# Schematic_openbook_v58.net
KiCad netlist of a schematic drawn in EAGLE
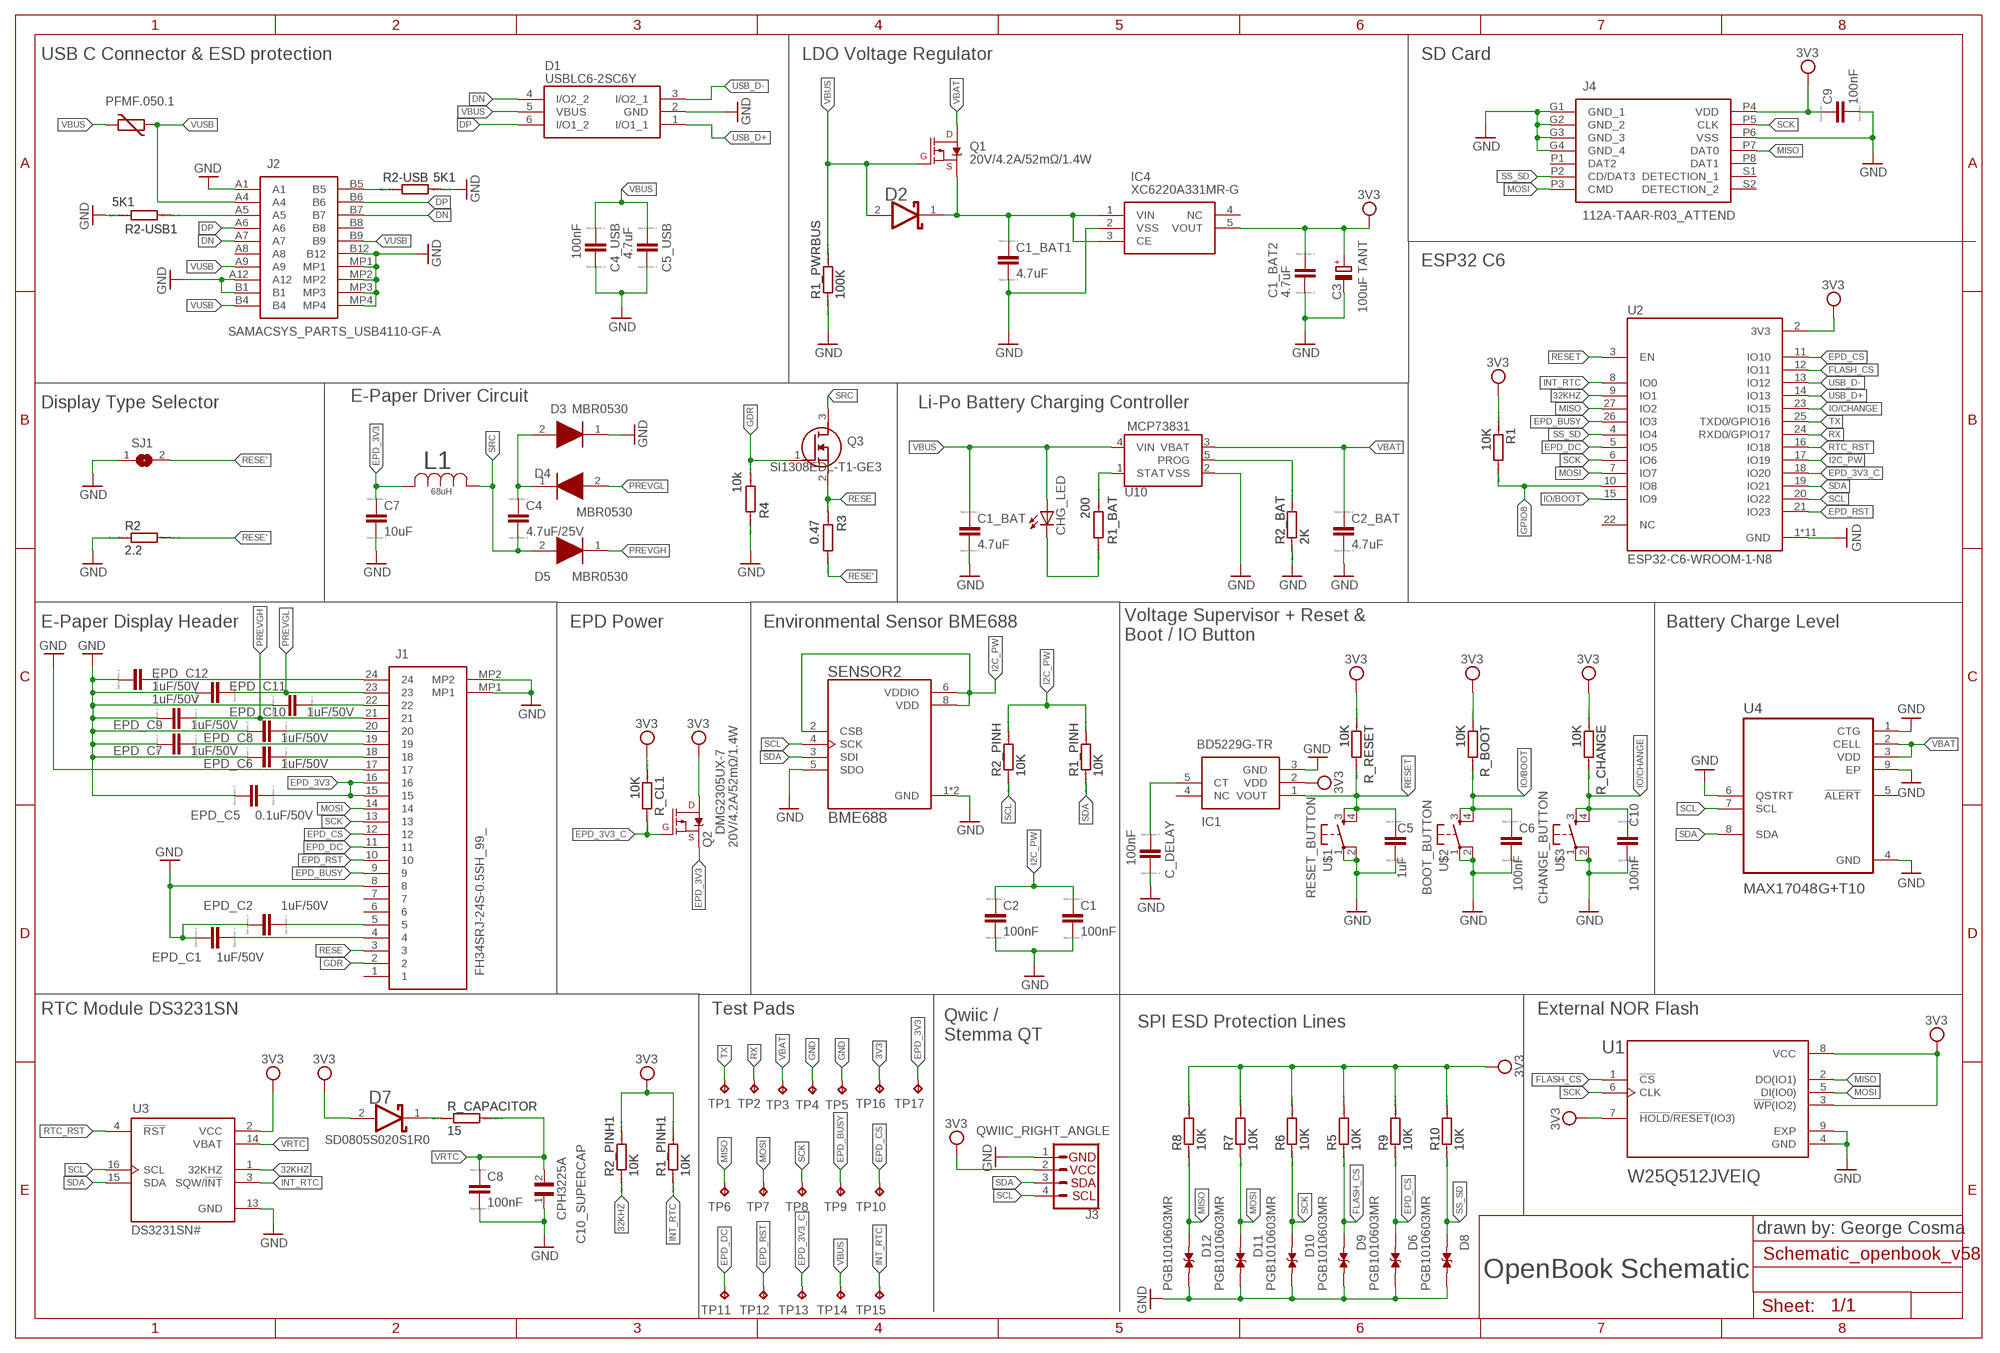
[diagram p0: schematic, sheet 1]

(export (version "E")
  (design (tool "Eeschema 10.0.6"))
  (components
    (comp (ref "C1")
      (value "100nF")
      (footprint "eagle-import:EAGLE-LTSPICE_C0402")
      (libsource (lib "eagle-import") (part "EAGLE-LTSPICE_CC0402"))
    )
    (comp (ref "C1_BAT")
      (value "4.7uF")
      (footprint "eagle-import:EAGLE-LTSPICE_C0402")
      (libsource (lib "eagle-import") (part "EAGLE-LTSPICE_CC0402"))
    )
    (comp (ref "C1_BAT1")
      (value "4.7uF")
      (footprint "eagle-import:EAGLE-LTSPICE_C0402")
      (libsource (lib "eagle-import") (part "EAGLE-LTSPICE_CC0402"))
    )
    (comp (ref "C1_BAT2")
      (value "4.7uF")
      (footprint "eagle-import:EAGLE-LTSPICE_C0402")
      (libsource (lib "eagle-import") (part "EAGLE-LTSPICE_CC0402"))
    )
    (comp (ref "C2")
      (value "100nF")
      (footprint "eagle-import:EAGLE-LTSPICE_C0402")
      (libsource (lib "eagle-import") (part "EAGLE-LTSPICE_CC0402"))
    )
    (comp (ref "C2_BAT")
      (value "4.7uF")
      (footprint "eagle-import:EAGLE-LTSPICE_C0402")
      (libsource (lib "eagle-import") (part "EAGLE-LTSPICE_CC0402"))
    )
    (comp (ref "C3")
      (value "100uF TANT")
      (footprint "eagle-import:RCL_CT3528")
      (libsource (lib "eagle-import") (part "RCL_CPOL-EUCT3528"))
    )
    (comp (ref "C4")
      (value "4.7uF/25V")
      (footprint "eagle-import:EAGLE-LTSPICE_C0402")
      (libsource (lib "eagle-import") (part "EAGLE-LTSPICE_CC0402"))
    )
    (comp (ref "C4_USB")
      (value "100nF")
      (footprint "eagle-import:EAGLE-LTSPICE_C0402")
      (libsource (lib "eagle-import") (part "EAGLE-LTSPICE_CC0402"))
    )
    (comp (ref "C5")
      (value "1uF")
      (footprint "eagle-import:EAGLE-LTSPICE_C0402")
      (libsource (lib "eagle-import") (part "EAGLE-LTSPICE_CC0402"))
    )
    (comp (ref "C5_USB")
      (value "4.7uF")
      (footprint "eagle-import:EAGLE-LTSPICE_C0402")
      (libsource (lib "eagle-import") (part "EAGLE-LTSPICE_CC0402"))
    )
    (comp (ref "C6")
      (value "100nF")
      (footprint "eagle-import:EAGLE-LTSPICE_C0402")
      (libsource (lib "eagle-import") (part "EAGLE-LTSPICE_CC0402"))
    )
    (comp (ref "C7")
      (value "10uF")
      (footprint "eagle-import:EAGLE-LTSPICE_C0402")
      (libsource (lib "eagle-import") (part "EAGLE-LTSPICE_CC0402"))
    )
    (comp (ref "C8")
      (value "100nF")
      (footprint "eagle-import:EAGLE-LTSPICE_C0402")
      (libsource (lib "eagle-import") (part "EAGLE-LTSPICE_CC0402"))
    )
    (comp (ref "C9")
      (value "100nF")
      (footprint "eagle-import:EAGLE-LTSPICE_C0402")
      (libsource (lib "eagle-import") (part "EAGLE-LTSPICE_CC0402"))
    )
    (comp (ref "C10")
      (value "100nF")
      (footprint "eagle-import:EAGLE-LTSPICE_C0402")
      (libsource (lib "eagle-import") (part "EAGLE-LTSPICE_CC0402"))
    )
    (comp (ref "C10_SUPERCAP")
      (value "CPH3225A")
      (footprint "eagle-import:CAPCP3225X100N")
      (fields (field (name "MF") "Seiko Instruments"))
      (libsource (lib "eagle-import") (part "CPH3225A"))
    )
    (comp (ref "CHG_LED")
      (value "NA")
      (footprint "eagle-import:ADAFRUIT_CHIP-LED0603")
      (libsource (lib "eagle-import") (part "ADAFRUIT_LEDCHIP-LED0603"))
    )
    (comp (ref "C_DELAY")
      (value "100nF")
      (footprint "eagle-import:EAGLE-LTSPICE_C0402")
      (libsource (lib "eagle-import") (part "EAGLE-LTSPICE_CC0402"))
    )
    (comp (ref "D1")
      (value "USBLC6-2SC6Y")
      (footprint "eagle-import:SOT95P280X145-6N")
      (fields (field (name "MF") "STMicroelectronics"))
      (libsource (lib "eagle-import") (part "USBLC6-2SC6Y"))
    )
    (comp (ref "D2")
      (value "ESP32_WROVER_AVX---SD0805S020S1R0_AVX_SD0805S020S1R0_0_0AVX_SD0805S020S1R0_0_0")
      (footprint "eagle-import:ESP32_WROVER_AVX---SD0805S020S1R0_AVX_SD0805S020S1R0_0")
      (fields
        (field (name "DIGIKEY_PART_NUMBER") "478-7800-1-ND")
        (field (name "MF") "AVX")
        (field (name "MOUSER_PART_NUMBER") "581-SD0805S020S1R0")
      )
      (libsource (lib "eagle-import") (part "ESP32_WROVER_AVX---SD0805S020S1R0_AVX_SD0805S020S1R0_0_0AVX_SD0805S020S1R0_0_0"))
    )
    (comp (ref "D3")
      (value "MBR0530")
      (footprint "eagle-import:SOD3716X135N")
      (fields (field (name "MF") "ON Semiconductor"))
      (libsource (lib "eagle-import") (part "MBR0530"))
    )
    (comp (ref "D4")
      (value "MBR0530")
      (footprint "eagle-import:SOD3716X135N")
      (fields (field (name "MF") "ON Semiconductor"))
      (libsource (lib "eagle-import") (part "MBR0530"))
    )
    (comp (ref "D5")
      (value "MBR0530")
      (footprint "eagle-import:SOD3716X135N")
      (fields (field (name "MF") "ON Semiconductor"))
      (libsource (lib "eagle-import") (part "MBR0530"))
    )
    (comp (ref "D6")
      (value "PGB1010603MR")
      (footprint "eagle-import:DIOC1608X36N")
      (fields (field (name "MF") "Littelfuse Inc."))
      (libsource (lib "eagle-import") (part "PGB1010603MR"))
    )
    (comp (ref "D7")
      (value "SD0805S020S1R0")
      (footprint "eagle-import:ESP32_WROVER_AVX---SD0805S020S1R0_AVX_SD0805S020S1R0_0")
      (fields
        (field (name "DIGIKEY_PART_NUMBER") "478-7800-1-ND")
        (field (name "MF") "AVX")
        (field (name "MOUSER_PART_NUMBER") "581-SD0805S020S1R0")
      )
      (libsource (lib "eagle-import") (part "ESP32_WROVER_AVX---SD0805S020S1R0_AVX_SD0805S020S1R0_0_0AVX_SD0805S020S1R0_0_0"))
    )
    (comp (ref "D8")
      (value "PGB1010603MR")
      (footprint "eagle-import:DIOC1608X36N")
      (fields (field (name "MF") "Littelfuse Inc."))
      (libsource (lib "eagle-import") (part "PGB1010603MR"))
    )
    (comp (ref "D9")
      (value "PGB1010603MR")
      (footprint "eagle-import:DIOC1608X36N")
      (fields (field (name "MF") "Littelfuse Inc."))
      (libsource (lib "eagle-import") (part "PGB1010603MR"))
    )
    (comp (ref "D10")
      (value "PGB1010603MR")
      (footprint "eagle-import:DIOC1608X36N")
      (fields (field (name "MF") "Littelfuse Inc."))
      (libsource (lib "eagle-import") (part "PGB1010603MR"))
    )
    (comp (ref "D11")
      (value "PGB1010603MR")
      (footprint "eagle-import:DIOC1608X36N")
      (fields (field (name "MF") "Littelfuse Inc."))
      (libsource (lib "eagle-import") (part "PGB1010603MR"))
    )
    (comp (ref "D12")
      (value "PGB1010603MR")
      (footprint "eagle-import:DIOC1608X36N")
      (fields (field (name "MF") "Littelfuse Inc."))
      (libsource (lib "eagle-import") (part "PGB1010603MR"))
    )
    (comp (ref "EPD_C1")
      (value "1uF/50V")
      (footprint "eagle-import:EAGLE-LTSPICE_C0402")
      (libsource (lib "eagle-import") (part "EAGLE-LTSPICE_CC0402"))
    )
    (comp (ref "EPD_C2")
      (value "1uF/50V")
      (footprint "eagle-import:EAGLE-LTSPICE_C0402")
      (libsource (lib "eagle-import") (part "EAGLE-LTSPICE_CC0402"))
    )
    (comp (ref "EPD_C5")
      (value "0.1uF/50V")
      (footprint "eagle-import:EAGLE-LTSPICE_C0402")
      (libsource (lib "eagle-import") (part "EAGLE-LTSPICE_CC0402"))
    )
    (comp (ref "EPD_C6")
      (value "1uF/50V")
      (footprint "eagle-import:EAGLE-LTSPICE_C0402")
      (libsource (lib "eagle-import") (part "EAGLE-LTSPICE_CC0402"))
    )
    (comp (ref "EPD_C7")
      (value "1uF/50V")
      (footprint "eagle-import:EAGLE-LTSPICE_C0402")
      (libsource (lib "eagle-import") (part "EAGLE-LTSPICE_CC0402"))
    )
    (comp (ref "EPD_C8")
      (value "1uF/50V")
      (footprint "eagle-import:EAGLE-LTSPICE_C0402")
      (libsource (lib "eagle-import") (part "EAGLE-LTSPICE_CC0402"))
    )
    (comp (ref "EPD_C9")
      (value "1uF/50V")
      (footprint "eagle-import:EAGLE-LTSPICE_C0402")
      (libsource (lib "eagle-import") (part "EAGLE-LTSPICE_CC0402"))
    )
    (comp (ref "EPD_C10")
      (value "1uF/50V")
      (footprint "eagle-import:EAGLE-LTSPICE_C0402")
      (libsource (lib "eagle-import") (part "EAGLE-LTSPICE_CC0402"))
    )
    (comp (ref "EPD_C11")
      (value "1uF/50V")
      (footprint "eagle-import:EAGLE-LTSPICE_C0402")
      (libsource (lib "eagle-import") (part "EAGLE-LTSPICE_CC0402"))
    )
    (comp (ref "EPD_C12")
      (value "1uF/50V")
      (footprint "eagle-import:EAGLE-LTSPICE_C0402")
      (libsource (lib "eagle-import") (part "EAGLE-LTSPICE_CC0402"))
    )
    (comp (ref "IC1")
      (value "BD5229G-TR")
      (footprint "eagle-import:SOT95P280X125-5N")
      (fields (field (name "MOUSER_PART_NUMBER") "755-BD5229G-TR"))
      (libsource (lib "eagle-import") (part "BD5229G-TR"))
    )
    (comp (ref "IC4")
      (value "XC6220A331MR-G")
      (footprint "eagle-import:SOT95P280X120-5N")
      (fields (field (name "MOUSER_PART_NUMBER") "865-XC6220A331MR-G"))
      (libsource (lib "eagle-import") (part "XC6220A331MR-G"))
    )
    (comp (ref "J1")
      (value "FH34SRJ-24S-0.5SH_99_")
      (footprint "eagle-import:FH34SRJ24S05SH99")
      (fields
        (field (name "MANUFACTURER_PART_NUMBER") "FH34SRJ-24S-0.5SH(99)")
        (field (name "MOUSER_PART_NUMBER") "798-FH34SRJ24S05SH99")
      )
      (libsource (lib "eagle-import") (part "FH34SRJ-24S-0.5SH_99_"))
    )
    (comp (ref "J2")
      (value "SAMACSYS_PARTS_USB4110-GF-A")
      (footprint "eagle-import:SAMACSYS_PARTS_USB4110GFA")
      (fields
        (field (name "MANUFACTURER_PART_NUMBER") "USB4110-GF-A")
        (field (name "MOUSER_PART_NUMBER") "640-USB4110-GF-A")
      )
      (libsource (lib "eagle-import") (part "SAMACSYS_PARTS_USB4110-GF-A"))
    )
    (comp (ref "J3")
      (value "QWIIC_RIGHT_ANGLE")
      (footprint "eagle-import:JST04_1MM_RA")
      (libsource (lib "eagle-import") (part "QWIIC_CONNECTORJS-1MM"))
    )
    (comp (ref "J4")
      (value "112A-TAAR-R03_ATTEND")
      (footprint "eagle-import:112ATAARR03ATTEND")
      (fields (field (name "MANUFACTURER_PART_NUMBER") "112A-TAAR-R03 ATTEND"))
      (libsource (lib "eagle-import") (part "112A-TAAR-R03_ATTEND"))
    )
    (comp (ref "L1")
      (value "68uH")
      (footprint "eagle-import:IND_4828-WE-TPC_WRE")
      (fields
        (field (name "MANUFACTURER_PART_NUMBER") "744043680")
        (field (name "COPYRIGHT") "Copyright (C) 2024 Ultra Librarian. All rights reserved.")
      )
      (libsource (lib "eagle-import") (part "744043680IND_4828-WE-TPC_WRE"))
    )
    (comp (ref "PFMF.050.1")
      (value "ESP32C6_VARISTORCN1812")
      (footprint "eagle-import:ESP32C6_VARISTOR_CT_CN1812")
      (libsource (lib "eagle-import") (part "ESP32C6_VARISTORCN1812"))
    )
    (comp (ref "Q1")
      (value "20V/4.2A/52mΩ/1.4W")
      (footprint "eagle-import:ESP32_WROVER_SPARKFUN-DISCRETESEMI_SOT23-3")
      (libsource (lib "eagle-import") (part "ESP32_WROVER_SPARKFUN-DISCRETESEMI_MOSFET_PCH-DMG2305UX-7"))
    )
    (comp (ref "Q2")
      (value "20V/4.2A/52mΩ/1.4W")
      (footprint "eagle-import:ESP32_WROVER_SPARKFUN-DISCRETESEMI_SOT23-3")
      (libsource (lib "eagle-import") (part "ESP32_WROVER_SPARKFUN-DISCRETESEMI_MOSFET_PCH-DMG2305UX-7"))
    )
    (comp (ref "Q3")
      (value "SI1308EDL-T1-GE3")
      (footprint "eagle-import:SOT65P210X110-3N")
      (fields (field (name "MF") "Vishay Siliconix"))
      (libsource (lib "eagle-import") (part "SI1308EDL-T1-GE3"))
    )
    (comp (ref "R1")
      (value "10K")
      (footprint "eagle-import:ESP32_WROVER_EAGLE-LTSPICE_R0402")
      (libsource (lib "eagle-import") (part "ESP32_WROVER_EAGLE-LTSPICE_RR0402"))
    )
    (comp (ref "R1_BAT")
      (value "200")
      (footprint "eagle-import:ESP32_WROVER_EAGLE-LTSPICE_R0402")
      (libsource (lib "eagle-import") (part "ESP32_WROVER_EAGLE-LTSPICE_RR0402"))
    )
    (comp (ref "R1_PINH")
      (value "10K")
      (footprint "eagle-import:ESP32_WROVER_EAGLE-LTSPICE_R0402")
      (libsource (lib "eagle-import") (part "ESP32_WROVER_EAGLE-LTSPICE_RR0402"))
    )
    (comp (ref "R1_PINH1")
      (value "10K")
      (footprint "eagle-import:ESP32_WROVER_EAGLE-LTSPICE_R0402")
      (libsource (lib "eagle-import") (part "ESP32_WROVER_EAGLE-LTSPICE_RR0402"))
    )
    (comp (ref "R1_PWRBUS")
      (value "100K")
      (footprint "eagle-import:ESP32_WROVER_EAGLE-LTSPICE_R0402")
      (libsource (lib "eagle-import") (part "ESP32_WROVER_EAGLE-LTSPICE_RR0402"))
    )
    (comp (ref "R2")
      (value "2.2")
      (footprint "eagle-import:ESP32_WROVER_EAGLE-LTSPICE_R0402")
      (libsource (lib "eagle-import") (part "ESP32_WROVER_EAGLE-LTSPICE_RR0402"))
    )
    (comp (ref "R2-USB")
      (value "5K1")
      (footprint "eagle-import:ESP32_WROVER_EAGLE-LTSPICE_R0402")
      (libsource (lib "eagle-import") (part "ESP32_WROVER_EAGLE-LTSPICE_RR0402"))
    )
    (comp (ref "R2-USB1")
      (value "5K1")
      (footprint "eagle-import:ESP32_WROVER_EAGLE-LTSPICE_R0402")
      (libsource (lib "eagle-import") (part "ESP32_WROVER_EAGLE-LTSPICE_RR0402"))
    )
    (comp (ref "R2_BAT")
      (value "2K")
      (footprint "eagle-import:ESP32_WROVER_EAGLE-LTSPICE_R0402")
      (libsource (lib "eagle-import") (part "ESP32_WROVER_EAGLE-LTSPICE_RR0402"))
    )
    (comp (ref "R2_PINH")
      (value "10K")
      (footprint "eagle-import:ESP32_WROVER_EAGLE-LTSPICE_R0402")
      (libsource (lib "eagle-import") (part "ESP32_WROVER_EAGLE-LTSPICE_RR0402"))
    )
    (comp (ref "R2_PINH1")
      (value "10K")
      (footprint "eagle-import:ESP32_WROVER_EAGLE-LTSPICE_R0402")
      (libsource (lib "eagle-import") (part "ESP32_WROVER_EAGLE-LTSPICE_RR0402"))
    )
    (comp (ref "R3")
      (value "0.47")
      (footprint "eagle-import:ESP32_WROVER_EAGLE-LTSPICE_R0402")
      (libsource (lib "eagle-import") (part "ESP32_WROVER_EAGLE-LTSPICE_RR0402"))
    )
    (comp (ref "R4")
      (value "10k")
      (footprint "eagle-import:ESP32_WROVER_EAGLE-LTSPICE_R0402")
      (libsource (lib "eagle-import") (part "ESP32_WROVER_EAGLE-LTSPICE_RR0402"))
    )
    (comp (ref "R5")
      (value "10K")
      (footprint "eagle-import:ESP32_WROVER_EAGLE-LTSPICE_R0402")
      (libsource (lib "eagle-import") (part "ESP32_WROVER_EAGLE-LTSPICE_RR0402"))
    )
    (comp (ref "R6")
      (value "10K")
      (footprint "eagle-import:ESP32_WROVER_EAGLE-LTSPICE_R0402")
      (libsource (lib "eagle-import") (part "ESP32_WROVER_EAGLE-LTSPICE_RR0402"))
    )
    (comp (ref "R7")
      (value "10K")
      (footprint "eagle-import:ESP32_WROVER_EAGLE-LTSPICE_R0402")
      (libsource (lib "eagle-import") (part "ESP32_WROVER_EAGLE-LTSPICE_RR0402"))
    )
    (comp (ref "R8")
      (value "10K")
      (footprint "eagle-import:ESP32_WROVER_EAGLE-LTSPICE_R0402")
      (libsource (lib "eagle-import") (part "ESP32_WROVER_EAGLE-LTSPICE_RR0402"))
    )
    (comp (ref "R9")
      (value "10K")
      (footprint "eagle-import:ESP32_WROVER_EAGLE-LTSPICE_R0402")
      (libsource (lib "eagle-import") (part "ESP32_WROVER_EAGLE-LTSPICE_RR0402"))
    )
    (comp (ref "R10")
      (value "10K")
      (footprint "eagle-import:ESP32_WROVER_EAGLE-LTSPICE_R0402")
      (libsource (lib "eagle-import") (part "ESP32_WROVER_EAGLE-LTSPICE_RR0402"))
    )
    (comp (ref "R_BOOT")
      (value "10K")
      (footprint "eagle-import:ESP32_WROVER_EAGLE-LTSPICE_R0402")
      (libsource (lib "eagle-import") (part "ESP32_WROVER_EAGLE-LTSPICE_RR0402"))
    )
    (comp (ref "R_CAPACITOR")
      (value "15")
      (footprint "eagle-import:ESP32_WROVER_EAGLE-LTSPICE_R0402")
      (libsource (lib "eagle-import") (part "ESP32_WROVER_EAGLE-LTSPICE_RR0402"))
    )
    (comp (ref "R_CHANGE")
      (value "10K")
      (footprint "eagle-import:ESP32_WROVER_EAGLE-LTSPICE_R0402")
      (libsource (lib "eagle-import") (part "ESP32_WROVER_EAGLE-LTSPICE_RR0402"))
    )
    (comp (ref "R_CL1")
      (value "10K")
      (footprint "eagle-import:ESP32_WROVER_EAGLE-LTSPICE_R0402")
      (libsource (lib "eagle-import") (part "ESP32_WROVER_EAGLE-LTSPICE_RR0402"))
    )
    (comp (ref "R_RESET")
      (value "10K")
      (footprint "eagle-import:ESP32_WROVER_EAGLE-LTSPICE_R0402")
      (libsource (lib "eagle-import") (part "ESP32_WROVER_EAGLE-LTSPICE_RR0402"))
    )
    (comp (ref "SENSOR2")
      (value "BME688")
      (footprint "eagle-import:ESP32_WROVER_BME680_PSON80P300X300X100-8N")
      (fields (field (name "MF") "Bosch Sensortec") (field (name "MP") "BME680"))
      (libsource (lib "eagle-import") (part "ESP32_WROVER_BME680_BME680"))
    )
    (comp (ref "SJ1") (value "NA") (footprint "eagle-import:SJ") (libsource (lib "eagle-import") (part "SJ")))
    (comp (ref "TP1")
      (value "TPTP20R")
      (footprint "eagle-import:TP20R")
      (libsource (lib "eagle-import") (part "TPTP20R"))
    )
    (comp (ref "TP2")
      (value "TPTP20R")
      (footprint "eagle-import:TP20R")
      (libsource (lib "eagle-import") (part "TPTP20R"))
    )
    (comp (ref "TP3")
      (value "TPTP20R")
      (footprint "eagle-import:TP20R")
      (libsource (lib "eagle-import") (part "TPTP20R"))
    )
    (comp (ref "TP4")
      (value "TPTP20R")
      (footprint "eagle-import:TP20R")
      (libsource (lib "eagle-import") (part "TPTP20R"))
    )
    (comp (ref "TP5")
      (value "TPTP20R")
      (footprint "eagle-import:TP20R")
      (libsource (lib "eagle-import") (part "TPTP20R"))
    )
    (comp (ref "TP6")
      (value "TPTP20R")
      (footprint "eagle-import:TP20R")
      (libsource (lib "eagle-import") (part "TPTP20R"))
    )
    (comp (ref "TP7")
      (value "TPTP20R")
      (footprint "eagle-import:TP20R")
      (libsource (lib "eagle-import") (part "TPTP20R"))
    )
    (comp (ref "TP8")
      (value "TPTP20R")
      (footprint "eagle-import:TP20R")
      (libsource (lib "eagle-import") (part "TPTP20R"))
    )
    (comp (ref "TP9")
      (value "TPTP20R")
      (footprint "eagle-import:TP20R")
      (libsource (lib "eagle-import") (part "TPTP20R"))
    )
    (comp (ref "TP10")
      (value "TPTP20R")
      (footprint "eagle-import:TP20R")
      (libsource (lib "eagle-import") (part "TPTP20R"))
    )
    (comp (ref "TP11")
      (value "TPTP20R")
      (footprint "eagle-import:TP20R")
      (libsource (lib "eagle-import") (part "TPTP20R"))
    )
    (comp (ref "TP12")
      (value "TPTP20R")
      (footprint "eagle-import:TP20R")
      (libsource (lib "eagle-import") (part "TPTP20R"))
    )
    (comp (ref "TP13")
      (value "TPTP20R")
      (footprint "eagle-import:TP20R")
      (libsource (lib "eagle-import") (part "TPTP20R"))
    )
    (comp (ref "TP14")
      (value "TPTP20R")
      (footprint "eagle-import:TP20R")
      (libsource (lib "eagle-import") (part "TPTP20R"))
    )
    (comp (ref "TP15")
      (value "TPTP20R")
      (footprint "eagle-import:TP20R")
      (libsource (lib "eagle-import") (part "TPTP20R"))
    )
    (comp (ref "TP16")
      (value "TPTP20R")
      (footprint "eagle-import:TP20R")
      (libsource (lib "eagle-import") (part "TPTP20R"))
    )
    (comp (ref "TP17")
      (value "TPTP20R")
      (footprint "eagle-import:TP20R")
      (libsource (lib "eagle-import") (part "TPTP20R"))
    )
    (comp (ref "U$1")
      (value "RESET_BUTTON")
      (footprint "eagle-import:MYBUTTON")
      (libsource (lib "eagle-import") (part "BUTTON_CUSYOMV1"))
    )
    (comp (ref "U$2")
      (value "BOOT_BUTTON")
      (footprint "eagle-import:MYBUTTON")
      (libsource (lib "eagle-import") (part "BUTTON_CUSYOMV1"))
    )
    (comp (ref "U$3")
      (value "CHANGE_BUTTON")
      (footprint "eagle-import:MYBUTTON")
      (libsource (lib "eagle-import") (part "BUTTON_CUSYOMV1"))
    )
    (comp (ref "U1")
      (value "W25Q512JVEIQ")
      (footprint "eagle-import:SON127P600X800X80-9N")
      (fields (field (name "MF") "Winbond Electronics"))
      (libsource (lib "eagle-import") (part "W25Q512JVEIQ"))
    )
    (comp (ref "U2")
      (value "ESP32-C6-WROOM-1-N8")
      (footprint "eagle-import:XCVR_ESP32-C6-WROOM-1-N8")
      (fields (field (name "MF") "Espressif Systems"))
      (libsource (lib "eagle-import") (part "ESP32-C6-WROOM-1-N8"))
    )
    (comp (ref "U3")
      (value "DS3231SN#")
      (footprint "eagle-import:SOIC127P1032X265-16N")
      (fields (field (name "MF") "Analog Devices"))
      (libsource (lib "eagle-import") (part "DS3231SN#"))
    )
    (comp (ref "U4")
      (value "MAX17048G+T10")
      (footprint "eagle-import:SON50P200X200X80-9N")
      (fields (field (name "MF") "Analog Devices"))
      (libsource (lib "eagle-import") (part "MAX17048G+T10"))
    )
    (comp (ref "U10")
      (value "MCP73831")
      (footprint "eagle-import:ESP32_WROVER_SPARKFUN-IC-POWER_SOT23-5")
      (libsource (lib "eagle-import") (part "ESP32_WROVER_SPARKFUN-IC-POWER_MCP73831"))
    )
  )
  (nets
    (net (code "1") (name "3V3") (class "Default")
      (node (ref "C1_BAT2") (pin "1") (pinfunction "1_1") (pintype "passive"))
      (node (ref "C3") (pin "+") (pinfunction "+_+") (pintype "passive"))
      (node (ref "C9") (pin "1") (pinfunction "1_1") (pintype "passive"))
      (node (ref "D7") (pin "2") (pinfunction "ANODE_2") (pintype "bidirectional"))
      (node (ref "IC1") (pin "2") (pinfunction "VDD_2") (pintype "bidirectional"))
      (node (ref "IC4") (pin "5") (pinfunction "VOUT_5") (pintype "bidirectional"))
      (node (ref "J3") (pin "2") (pinfunction "2_2") (pintype "power_in"))
      (node (ref "J4") (pin "P4") (pinfunction "VDD_P4") (pintype "bidirectional"))
      (node (ref "Q2") (pin "3") (pinfunction "D_3") (pintype "bidirectional"))
      (node (ref "R1") (pin "1") (pinfunction "1_1") (pintype "passive"))
      (node (ref "R10") (pin "2") (pinfunction "2_2") (pintype "passive"))
      (node (ref "R1_PINH1") (pin "2") (pinfunction "2_2") (pintype "passive"))
      (node (ref "R2_PINH1") (pin "2") (pinfunction "2_2") (pintype "passive"))
      (node (ref "R5") (pin "2") (pinfunction "2_2") (pintype "passive"))
      (node (ref "R6") (pin "2") (pinfunction "2_2") (pintype "passive"))
      (node (ref "R7") (pin "2") (pinfunction "2_2") (pintype "passive"))
      (node (ref "R8") (pin "2") (pinfunction "2_2") (pintype "passive"))
      (node (ref "R9") (pin "2") (pinfunction "2_2") (pintype "passive"))
      (node (ref "R_BOOT") (pin "1") (pinfunction "1_1") (pintype "passive"))
      (node (ref "R_CHANGE") (pin "1") (pinfunction "1_1") (pintype "passive"))
      (node (ref "R_CL1") (pin "1") (pinfunction "1_1") (pintype "passive"))
      (node (ref "R_RESET") (pin "1") (pinfunction "1_1") (pintype "passive"))
      (node (ref "TP16") (pin "TP") (pinfunction "TP_TP") (pintype "input"))
      (node (ref "U1") (pin "3") (pinfunction "~{WP}(IO2)_3") (pintype "bidirectional"))
      (node (ref "U1") (pin "7") (pinfunction "~{HOLD}/~{RESET}(IO3)_7") (pintype "bidirectional"))
      (node (ref "U1") (pin "8") (pinfunction "VCC_8") (pintype "power_in"))
      (node (ref "U2") (pin "2") (pinfunction "3V3_2") (pintype "power_in"))
      (node (ref "U3") (pin "2") (pinfunction "VCC_2") (pintype "power_in"))
    )
    (net (code "2") (name "32KHZ") (class "Default")
      (node (ref "R2_PINH1") (pin "1") (pinfunction "1_1") (pintype "passive"))
      (node (ref "U2") (pin "9") (pinfunction "IO1_9") (pintype "bidirectional"))
      (node (ref "U3") (pin "1") (pinfunction "32KHZ_1") (pintype "output"))
    )
    (net (code "3") (name "DN") (class "Default")
      (node (ref "D1") (pin "4") (pinfunction "I/O2_2_4") (pintype "bidirectional"))
      (node (ref "J2") (pin "A7") (pinfunction "A7_A7") (pintype "bidirectional"))
      (node (ref "J2") (pin "B7") (pinfunction "B7_B7") (pintype "bidirectional"))
    )
    (net (code "4") (name "DP") (class "Default")
      (node (ref "D1") (pin "6") (pinfunction "I/O1_2_6") (pintype "bidirectional"))
      (node (ref "J2") (pin "A6") (pinfunction "A6_A6") (pintype "bidirectional"))
      (node (ref "J2") (pin "B6") (pinfunction "B6_B6") (pintype "bidirectional"))
    )
    (net (code "5") (name "EPD_3V3") (class "Default")
      (node (ref "C7") (pin "1") (pinfunction "1_1") (pintype "passive"))
      (node (ref "EPD_C5") (pin "1") (pinfunction "1_1") (pintype "passive"))
      (node (ref "J1") (pin "15") (pinfunction "15_15") (pintype "bidirectional"))
      (node (ref "J1") (pin "16") (pinfunction "16_16") (pintype "bidirectional"))
      (node (ref "L1") (pin "2") (pinfunction "2_2") (pintype "passive"))
      (node (ref "Q2") (pin "2") (pinfunction "S_2") (pintype "bidirectional"))
      (node (ref "TP17") (pin "TP") (pinfunction "TP_TP") (pintype "input"))
    )
    (net (code "6") (name "EPD_3V3_C") (class "Default")
      (node (ref "Q2") (pin "1") (pinfunction "G_1") (pintype "bidirectional"))
      (node (ref "R_CL1") (pin "2") (pinfunction "2_2") (pintype "passive"))
      (node (ref "TP13") (pin "TP") (pinfunction "TP_TP") (pintype "input"))
      (node (ref "U2") (pin "18") (pinfunction "IO20_18") (pintype "bidirectional"))
    )
    (net (code "7") (name "EPD_BUSY") (class "Default")
      (node (ref "J1") (pin "9") (pinfunction "9_9") (pintype "bidirectional"))
      (node (ref "TP9") (pin "TP") (pinfunction "TP_TP") (pintype "input"))
      (node (ref "U2") (pin "26") (pinfunction "IO3_26") (pintype "bidirectional"))
    )
    (net (code "8") (name "EPD_CS") (class "Default")
      (node (ref "D6") (pin "1") (pinfunction "1_1") (pintype "passive"))
      (node (ref "J1") (pin "12") (pinfunction "12_12") (pintype "bidirectional"))
      (node (ref "R9") (pin "1") (pinfunction "1_1") (pintype "passive"))
      (node (ref "TP10") (pin "TP") (pinfunction "TP_TP") (pintype "input"))
      (node (ref "U2") (pin "11") (pinfunction "IO10_11") (pintype "bidirectional"))
    )
    (net (code "9") (name "EPD_DC") (class "Default")
      (node (ref "J1") (pin "11") (pinfunction "11_11") (pintype "bidirectional"))
      (node (ref "TP11") (pin "TP") (pinfunction "TP_TP") (pintype "input"))
      (node (ref "U2") (pin "5") (pinfunction "IO5_5") (pintype "bidirectional"))
    )
    (net (code "10") (name "EPD_RST") (class "Default")
      (node (ref "J1") (pin "10") (pinfunction "10_10") (pintype "bidirectional"))
      (node (ref "TP12") (pin "TP") (pinfunction "TP_TP") (pintype "input"))
      (node (ref "U2") (pin "21") (pinfunction "IO23_21") (pintype "bidirectional"))
    )
    (net (code "11") (name "FLASH_CS") (class "Default")
      (node (ref "D9") (pin "1") (pinfunction "1_1") (pintype "passive"))
      (node (ref "R5") (pin "1") (pinfunction "1_1") (pintype "passive"))
      (node (ref "U1") (pin "1") (pinfunction "~{CS}_1") (pintype "input"))
      (node (ref "U2") (pin "12") (pinfunction "IO11_12") (pintype "bidirectional"))
    )
    (net (code "12") (name "GDR") (class "Default")
      (node (ref "J1") (pin "2") (pinfunction "2_2") (pintype "bidirectional"))
      (node (ref "Q3") (pin "1") (pinfunction "G_1") (pintype "bidirectional"))
      (node (ref "R4") (pin "2") (pinfunction "2_2") (pintype "passive"))
    )
    (net (code "13") (name "GND") (class "Default")
      (node (ref "C1") (pin "2") (pinfunction "2_2") (pintype "passive"))
      (node (ref "C10") (pin "2") (pinfunction "2_2") (pintype "passive"))
      (node (ref "C10_SUPERCAP") (pin "1") (pinfunction "1_1") (pintype "passive"))
      (node (ref "C1_BAT") (pin "2") (pinfunction "2_2") (pintype "passive"))
      (node (ref "C1_BAT1") (pin "2") (pinfunction "2_2") (pintype "passive"))
      (node (ref "C1_BAT2") (pin "2") (pinfunction "2_2") (pintype "passive"))
      (node (ref "C2") (pin "2") (pinfunction "2_2") (pintype "passive"))
      (node (ref "C2_BAT") (pin "2") (pinfunction "2_2") (pintype "passive"))
      (node (ref "C3") (pin "-") (pinfunction "-_-") (pintype "passive"))
      (node (ref "C4_USB") (pin "2") (pinfunction "2_2") (pintype "passive"))
      (node (ref "C5") (pin "2") (pinfunction "2_2") (pintype "passive"))
      (node (ref "C5_USB") (pin "2") (pinfunction "2_2") (pintype "passive"))
      (node (ref "C6") (pin "2") (pinfunction "2_2") (pintype "passive"))
      (node (ref "C7") (pin "2") (pinfunction "2_2") (pintype "passive"))
      (node (ref "C8") (pin "2") (pinfunction "2_2") (pintype "passive"))
      (node (ref "C9") (pin "2") (pinfunction "2_2") (pintype "passive"))
      (node (ref "C_DELAY") (pin "2") (pinfunction "2_2") (pintype "passive"))
      (node (ref "D1") (pin "2") (pinfunction "GND_2") (pintype "bidirectional"))
      (node (ref "D10") (pin "2") (pinfunction "2_2") (pintype "passive"))
      (node (ref "D11") (pin "2") (pinfunction "2_2") (pintype "passive"))
      (node (ref "D12") (pin "2") (pinfunction "2_2") (pintype "passive"))
      (node (ref "D4") (pin "1") (pinfunction "K_1") (pintype "bidirectional"))
      (node (ref "D6") (pin "2") (pinfunction "2_2") (pintype "passive"))
      (node (ref "D8") (pin "2") (pinfunction "2_2") (pintype "passive"))
      (node (ref "D9") (pin "2") (pinfunction "2_2") (pintype "passive"))
      (node (ref "EPD_C1") (pin "2") (pinfunction "2_2") (pintype "passive"))
      (node (ref "EPD_C10") (pin "2") (pinfunction "2_2") (pintype "passive"))
      (node (ref "EPD_C11") (pin "2") (pinfunction "2_2") (pintype "passive"))
      (node (ref "EPD_C12") (pin "2") (pinfunction "2_2") (pintype "passive"))
      (node (ref "EPD_C2") (pin "2") (pinfunction "2_2") (pintype "passive"))
      (node (ref "EPD_C5") (pin "2") (pinfunction "2_2") (pintype "passive"))
      (node (ref "EPD_C6") (pin "2") (pinfunction "2_2") (pintype "passive"))
      (node (ref "EPD_C7") (pin "2") (pinfunction "2_2") (pintype "passive"))
      (node (ref "EPD_C8") (pin "2") (pinfunction "2_2") (pintype "passive"))
      (node (ref "EPD_C9") (pin "2") (pinfunction "2_2") (pintype "passive"))
      (node (ref "IC1") (pin "3") (pinfunction "GND_3") (pintype "bidirectional"))
      (node (ref "IC4") (pin "2") (pinfunction "VSS_2") (pintype "bidirectional"))
      (node (ref "J1") (pin "17") (pinfunction "17_17") (pintype "bidirectional"))
      (node (ref "J1") (pin "8") (pinfunction "8_8") (pintype "bidirectional"))
      (node (ref "J1") (pin "MP1") (pinfunction "MP1_MP1") (pintype "bidirectional"))
      (node (ref "J1") (pin "MP2") (pinfunction "MP2_MP2") (pintype "bidirectional"))
      (node (ref "J2") (pin "A1") (pinfunction "A1_A1") (pintype "bidirectional"))
      (node (ref "J2") (pin "A12") (pinfunction "A12_A12") (pintype "bidirectional"))
      (node (ref "J2") (pin "B1") (pinfunction "B1_B1") (pintype "bidirectional"))
      (node (ref "J2") (pin "B12") (pinfunction "B12_B12") (pintype "bidirectional"))
      (node (ref "J2") (pin "MP1") (pinfunction "MP1_MP1") (pintype "bidirectional"))
      (node (ref "J2") (pin "MP2") (pinfunction "MP2_MP2") (pintype "bidirectional"))
      (node (ref "J2") (pin "MP3") (pinfunction "MP3_MP3") (pintype "bidirectional"))
      (node (ref "J2") (pin "MP4") (pinfunction "MP4_MP4") (pintype "bidirectional"))
      (node (ref "J3") (pin "1") (pinfunction "1_1") (pintype "power_in"))
      (node (ref "J4") (pin "G1") (pinfunction "GND_1_G1") (pintype "bidirectional"))
      (node (ref "J4") (pin "G2") (pinfunction "GND_2_G2") (pintype "bidirectional"))
      (node (ref "J4") (pin "G3") (pinfunction "GND_3_G3") (pintype "bidirectional"))
      (node (ref "J4") (pin "G4") (pinfunction "GND_4_G4") (pintype "bidirectional"))
      (node (ref "J4") (pin "P6") (pinfunction "VSS_P6") (pintype "bidirectional"))
      (node (ref "R1_PWRBUS") (pin "1") (pinfunction "1_1") (pintype "passive"))
      (node (ref "R2") (pin "1") (pinfunction "1_1") (pintype "passive"))
      (node (ref "R2-USB") (pin "2") (pinfunction "2_2") (pintype "passive"))
      (node (ref "R2-USB1") (pin "1") (pinfunction "1_1") (pintype "passive"))
      (node (ref "R2_BAT") (pin "1") (pinfunction "1_1") (pintype "passive"))
      (node (ref "R4") (pin "1") (pinfunction "1_1") (pintype "passive"))
      (node (ref "SENSOR2") (pin "1") (pinfunction "GND_1") (pintype "power_in"))
      (node (ref "SENSOR2") (pin "5") (pinfunction "SDO_5") (pintype "bidirectional"))
      (node (ref "SENSOR2") (pin "7") (pinfunction "GND_7") (pintype "power_in"))
      (node (ref "SJ1") (pin "1") (pinfunction "1_1") (pintype "passive"))
      (node (ref "TP4") (pin "TP") (pinfunction "TP_TP") (pintype "input"))
      (node (ref "TP5") (pin "TP") (pinfunction "TP_TP") (pintype "input"))
      (node (ref "U$1") (pin "1") (pinfunction "1_1") (pintype "passive"))
      (node (ref "U$1") (pin "2") (pinfunction "2_2") (pintype "passive"))
      (node (ref "U$2") (pin "1") (pinfunction "1_1") (pintype "passive"))
      (node (ref "U$2") (pin "2") (pinfunction "2_2") (pintype "passive"))
      (node (ref "U$3") (pin "1") (pinfunction "1_1") (pintype "passive"))
      (node (ref "U$3") (pin "2") (pinfunction "2_2") (pintype "passive"))
      (node (ref "U1") (pin "4") (pinfunction "GND_4") (pintype "power_in"))
      (node (ref "U1") (pin "9") (pinfunction "EXP_9") (pintype "passive"))
      (node (ref "U10") (pin "2") (pinfunction "VSS_2") (pintype "power_in"))
      (node (ref "U2") (pin "1") (pinfunction "GND_1") (pintype "power_in"))
      (node (ref "U2") (pin "28") (pinfunction "GND_28") (pintype "power_in"))
      (node (ref "U2") (pin "29_1") (pinfunction "GND_29_1") (pintype "power_in"))
      (node (ref "U2") (pin "29_2") (pinfunction "GND_29_2") (pintype "power_in"))
      (node (ref "U2") (pin "29_3") (pinfunction "GND_29_3") (pintype "power_in"))
      (node (ref "U2") (pin "29_4") (pinfunction "GND_29_4") (pintype "power_in"))
      (node (ref "U2") (pin "29_5") (pinfunction "GND_29_5") (pintype "power_in"))
      (node (ref "U2") (pin "29_6") (pinfunction "GND_29_6") (pintype "power_in"))
      (node (ref "U2") (pin "29_7") (pinfunction "GND_29_7") (pintype "power_in"))
      (node (ref "U2") (pin "29_8") (pinfunction "GND_29_8") (pintype "power_in"))
      (node (ref "U2") (pin "29_9") (pinfunction "GND_29_9") (pintype "power_in"))
      (node (ref "U3") (pin "13") (pinfunction "GND_13") (pintype "power_in"))
      (node (ref "U4") (pin "1") (pinfunction "CTG_1") (pintype "power_in"))
      (node (ref "U4") (pin "4") (pinfunction "GND_4") (pintype "power_in"))
      (node (ref "U4") (pin "6") (pinfunction "QSTRT_6") (pintype "input"))
      (node (ref "U4") (pin "9") (pinfunction "EP_9") (pintype "power_in"))
    )
    (net (code "14") (name "GPIO8") (class "Default")
      (node (ref "R1") (pin "2") (pinfunction "2_2") (pintype "passive"))
      (node (ref "U2") (pin "10") (pinfunction "IO8_10") (pintype "bidirectional"))
    )
    (net (code "15") (name "I2C_PW") (class "Default")
      (node (ref "C1") (pin "1") (pinfunction "1_1") (pintype "passive"))
      (node (ref "C2") (pin "1") (pinfunction "1_1") (pintype "passive"))
      (node (ref "R1_PINH") (pin "2") (pinfunction "2_2") (pintype "passive"))
      (node (ref "R2_PINH") (pin "2") (pinfunction "2_2") (pintype "passive"))
      (node (ref "SENSOR2") (pin "2") (pinfunction "CSB_2") (pintype "input"))
      (node (ref "SENSOR2") (pin "6") (pinfunction "VDDIO_6") (pintype "power_in"))
      (node (ref "SENSOR2") (pin "8") (pinfunction "VDD_8") (pintype "power_in"))
      (node (ref "U2") (pin "17") (pinfunction "IO19_17") (pintype "bidirectional"))
    )
    (net (code "16") (name "INT_RTC") (class "Default")
      (node (ref "R1_PINH1") (pin "1") (pinfunction "1_1") (pintype "passive"))
      (node (ref "TP15") (pin "TP") (pinfunction "TP_TP") (pintype "input"))
      (node (ref "U2") (pin "8") (pinfunction "IO0_8") (pintype "bidirectional"))
      (node (ref "U3") (pin "3") (pinfunction "SQW/~{INT}_3") (pintype "output"))
    )
    (net (code "17") (name "IO{slash}BOOT") (class "Default")
      (node (ref "C6") (pin "1") (pinfunction "1_1") (pintype "passive"))
      (node (ref "R_BOOT") (pin "2") (pinfunction "2_2") (pintype "passive"))
      (node (ref "U$2") (pin "3") (pinfunction "3_3") (pintype "passive"))
      (node (ref "U$2") (pin "4") (pinfunction "4_4") (pintype "passive"))
      (node (ref "U2") (pin "15") (pinfunction "IO9_15") (pintype "bidirectional"))
    )
    (net (code "18") (name "IO{slash}CHANGE") (class "Default")
      (node (ref "C10") (pin "1") (pinfunction "1_1") (pintype "passive"))
      (node (ref "R_CHANGE") (pin "2") (pinfunction "2_2") (pintype "passive"))
      (node (ref "U$3") (pin "3") (pinfunction "3_3") (pintype "passive"))
      (node (ref "U$3") (pin "4") (pinfunction "4_4") (pintype "passive"))
      (node (ref "U2") (pin "23") (pinfunction "IO15_23") (pintype "bidirectional"))
    )
    (net (code "19") (name "MISO") (class "Default")
      (node (ref "D12") (pin "1") (pinfunction "1_1") (pintype "passive"))
      (node (ref "J4") (pin "P7") (pinfunction "DAT0_P7") (pintype "bidirectional"))
      (node (ref "R8") (pin "1") (pinfunction "1_1") (pintype "passive"))
      (node (ref "TP6") (pin "TP") (pinfunction "TP_TP") (pintype "input"))
      (node (ref "U1") (pin "2") (pinfunction "DO(IO1)_2") (pintype "bidirectional"))
      (node (ref "U2") (pin "27") (pinfunction "IO2_27") (pintype "bidirectional"))
    )
    (net (code "20") (name "MOSI") (class "Default")
      (node (ref "D11") (pin "1") (pinfunction "1_1") (pintype "passive"))
      (node (ref "J1") (pin "14") (pinfunction "14_14") (pintype "bidirectional"))
      (node (ref "J4") (pin "P3") (pinfunction "CMD_P3") (pintype "bidirectional"))
      (node (ref "R7") (pin "1") (pinfunction "1_1") (pintype "passive"))
      (node (ref "TP7") (pin "TP") (pinfunction "TP_TP") (pintype "input"))
      (node (ref "U1") (pin "5") (pinfunction "DI(IO0)_5") (pintype "bidirectional"))
      (node (ref "U2") (pin "7") (pinfunction "IO7_7") (pintype "bidirectional"))
    )
    (net (code "21") (name "Net-(CHG_LED-PadC)") (class "Default")
      (node (ref "CHG_LED") (pin "C") (pinfunction "C_C") (pintype "passive"))
      (node (ref "R1_BAT") (pin "1") (pinfunction "1_1") (pintype "passive"))
    )
    (net (code "22") (name "Net-(D2-CATHODE)") (class "Default")
      (node (ref "C1_BAT1") (pin "1") (pinfunction "1_1") (pintype "passive"))
      (node (ref "D2") (pin "1") (pinfunction "CATHODE_1") (pintype "bidirectional"))
      (node (ref "IC4") (pin "1") (pinfunction "VIN_1") (pintype "bidirectional"))
      (node (ref "IC4") (pin "3") (pinfunction "CE_3") (pintype "bidirectional"))
      (node (ref "Q1") (pin "2") (pinfunction "S_2") (pintype "bidirectional"))
    )
    (net (code "23") (name "Net-(D3-K)") (class "Default")
      (node (ref "C4") (pin "1") (pinfunction "1_1") (pintype "passive"))
      (node (ref "D3") (pin "1") (pinfunction "K_1") (pintype "bidirectional"))
      (node (ref "D4") (pin "2") (pinfunction "A_2") (pintype "bidirectional"))
    )
    (net (code "24") (name "Net-(D7-CATHODE)") (class "Default")
      (node (ref "D7") (pin "1") (pinfunction "CATHODE_1") (pintype "bidirectional"))
      (node (ref "R_CAPACITOR") (pin "1") (pinfunction "1_1") (pintype "passive"))
    )
    (net (code "25") (name "Net-(EPD_C1-Pad1)") (class "Default")
      (node (ref "EPD_C1") (pin "1") (pinfunction "1_1") (pintype "passive"))
      (node (ref "J1") (pin "4") (pinfunction "4_4") (pintype "bidirectional"))
    )
    (net (code "26") (name "Net-(EPD_C2-Pad1)") (class "Default")
      (node (ref "EPD_C2") (pin "1") (pinfunction "1_1") (pintype "passive"))
      (node (ref "J1") (pin "5") (pinfunction "5_5") (pintype "bidirectional"))
    )
    (net (code "27") (name "Net-(EPD_C6-Pad1)") (class "Default")
      (node (ref "EPD_C6") (pin "1") (pinfunction "1_1") (pintype "passive"))
      (node (ref "J1") (pin "18") (pinfunction "18_18") (pintype "bidirectional"))
    )
    (net (code "28") (name "Net-(EPD_C7-Pad1)") (class "Default")
      (node (ref "EPD_C7") (pin "1") (pinfunction "1_1") (pintype "passive"))
      (node (ref "J1") (pin "19") (pinfunction "19_19") (pintype "bidirectional"))
    )
    (net (code "29") (name "Net-(EPD_C8-Pad1)") (class "Default")
      (node (ref "EPD_C8") (pin "1") (pinfunction "1_1") (pintype "passive"))
      (node (ref "J1") (pin "20") (pinfunction "20_20") (pintype "bidirectional"))
    )
    (net (code "30") (name "Net-(EPD_C10-Pad1)") (class "Default")
      (node (ref "EPD_C10") (pin "1") (pinfunction "1_1") (pintype "passive"))
      (node (ref "J1") (pin "22") (pinfunction "22_22") (pintype "bidirectional"))
    )
    (net (code "31") (name "Net-(EPD_C12-Pad1)") (class "Default")
      (node (ref "EPD_C12") (pin "1") (pinfunction "1_1") (pintype "passive"))
      (node (ref "J1") (pin "24") (pinfunction "24_24") (pintype "bidirectional"))
    )
    (net (code "32") (name "Net-(IC1-CT)") (class "Default")
      (node (ref "C_DELAY") (pin "1") (pinfunction "1_1") (pintype "passive"))
      (node (ref "IC1") (pin "5") (pinfunction "CT_5") (pintype "bidirectional"))
    )
    (net (code "33") (name "Net-(J2-PadA5)") (class "Default")
      (node (ref "J2") (pin "A5") (pinfunction "A5_A5") (pintype "bidirectional"))
      (node (ref "R2-USB1") (pin "2") (pinfunction "2_2") (pintype "passive"))
    )
    (net (code "34") (name "Net-(J2-PadB5)") (class "Default")
      (node (ref "J2") (pin "B5") (pinfunction "B5_B5") (pintype "bidirectional"))
      (node (ref "R2-USB") (pin "1") (pinfunction "1_1") (pintype "passive"))
    )
    (net (code "35") (name "Net-(U10-PROG)") (class "Default")
      (node (ref "R2_BAT") (pin "2") (pinfunction "2_2") (pintype "passive"))
      (node (ref "U10") (pin "5") (pinfunction "PROG_5") (pintype "input"))
    )
    (net (code "36") (name "Net-(U10-STAT)") (class "Default")
      (node (ref "R1_BAT") (pin "2") (pinfunction "2_2") (pintype "passive"))
      (node (ref "U10") (pin "1") (pinfunction "STAT_1") (pintype "output"))
    )
    (net (code "37") (name "PREVGH") (class "Default")
      (node (ref "D5") (pin "1") (pinfunction "K_1") (pintype "bidirectional"))
      (node (ref "EPD_C9") (pin "1") (pinfunction "1_1") (pintype "passive"))
      (node (ref "J1") (pin "21") (pinfunction "21_21") (pintype "bidirectional"))
    )
    (net (code "38") (name "PREVGL") (class "Default")
      (node (ref "D3") (pin "2") (pinfunction "A_2") (pintype "bidirectional"))
      (node (ref "EPD_C11") (pin "1") (pinfunction "1_1") (pintype "passive"))
      (node (ref "J1") (pin "23") (pinfunction "23_23") (pintype "bidirectional"))
    )
    (net (code "39") (name "RESE") (class "Default")
      (node (ref "J1") (pin "3") (pinfunction "3_3") (pintype "bidirectional"))
      (node (ref "Q3") (pin "2") (pinfunction "S_2") (pintype "bidirectional"))
      (node (ref "R3") (pin "2") (pinfunction "2_2") (pintype "passive"))
    )
    (net (code "40") (name "RESE'") (class "Default")
      (node (ref "R2") (pin "2") (pinfunction "2_2") (pintype "passive"))
      (node (ref "R3") (pin "1") (pinfunction "1_1") (pintype "passive"))
      (node (ref "SJ1") (pin "2") (pinfunction "2_2") (pintype "passive"))
    )
    (net (code "41") (name "RESET") (class "Default")
      (node (ref "C5") (pin "1") (pinfunction "1_1") (pintype "passive"))
      (node (ref "IC1") (pin "1") (pinfunction "VOUT_1") (pintype "bidirectional"))
      (node (ref "R_RESET") (pin "2") (pinfunction "2_2") (pintype "passive"))
      (node (ref "U$1") (pin "3") (pinfunction "3_3") (pintype "passive"))
      (node (ref "U$1") (pin "4") (pinfunction "4_4") (pintype "passive"))
      (node (ref "U2") (pin "3") (pinfunction "EN_3") (pintype "input"))
    )
    (net (code "42") (name "RTC_RST") (class "Default")
      (node (ref "U2") (pin "16") (pinfunction "IO18_16") (pintype "bidirectional"))
      (node (ref "U3") (pin "4") (pinfunction "~{RST}_4") (pintype "input"))
    )
    (net (code "43") (name "RX") (class "Default")
      (node (ref "TP2") (pin "TP") (pinfunction "TP_TP") (pintype "input"))
      (node (ref "U2") (pin "24") (pinfunction "RXD0/GPIO17_24") (pintype "bidirectional"))
    )
    (net (code "44") (name "SCK") (class "Default")
      (node (ref "D10") (pin "1") (pinfunction "1_1") (pintype "passive"))
      (node (ref "J1") (pin "13") (pinfunction "13_13") (pintype "bidirectional"))
      (node (ref "J4") (pin "P5") (pinfunction "CLK_P5") (pintype "bidirectional"))
      (node (ref "R6") (pin "1") (pinfunction "1_1") (pintype "passive"))
      (node (ref "TP8") (pin "TP") (pinfunction "TP_TP") (pintype "input"))
      (node (ref "U1") (pin "6") (pinfunction "CLK_6") (pintype "input"))
      (node (ref "U2") (pin "6") (pinfunction "IO6_6") (pintype "bidirectional"))
    )
    (net (code "45") (name "SCL") (class "Default")
      (node (ref "J3") (pin "4") (pinfunction "4_4") (pintype "passive"))
      (node (ref "R2_PINH") (pin "1") (pinfunction "1_1") (pintype "passive"))
      (node (ref "SENSOR2") (pin "4") (pinfunction "SCK_4") (pintype "input"))
      (node (ref "U2") (pin "20") (pinfunction "IO22_20") (pintype "bidirectional"))
      (node (ref "U3") (pin "16") (pinfunction "SCL_16") (pintype "input"))
      (node (ref "U4") (pin "7") (pinfunction "SCL_7") (pintype "input"))
    )
    (net (code "46") (name "SDA") (class "Default")
      (node (ref "J3") (pin "3") (pinfunction "3_3") (pintype "passive"))
      (node (ref "R1_PINH") (pin "1") (pinfunction "1_1") (pintype "passive"))
      (node (ref "SENSOR2") (pin "3") (pinfunction "SDI_3") (pintype "bidirectional"))
      (node (ref "U2") (pin "19") (pinfunction "IO21_19") (pintype "bidirectional"))
      (node (ref "U3") (pin "15") (pinfunction "SDA_15") (pintype "bidirectional"))
      (node (ref "U4") (pin "8") (pinfunction "SDA_8") (pintype "bidirectional"))
    )
    (net (code "47") (name "SRC") (class "Default")
      (node (ref "C4") (pin "2") (pinfunction "2_2") (pintype "passive"))
      (node (ref "D5") (pin "2") (pinfunction "A_2") (pintype "bidirectional"))
      (node (ref "L1") (pin "1") (pinfunction "1_1") (pintype "passive"))
      (node (ref "Q3") (pin "3") (pinfunction "D_3") (pintype "bidirectional"))
    )
    (net (code "48") (name "SS_SD") (class "Default")
      (node (ref "D8") (pin "1") (pinfunction "1_1") (pintype "passive"))
      (node (ref "J4") (pin "P2") (pinfunction "CD/DAT3_P2") (pintype "bidirectional"))
      (node (ref "R10") (pin "1") (pinfunction "1_1") (pintype "passive"))
      (node (ref "U2") (pin "4") (pinfunction "IO4_4") (pintype "bidirectional"))
    )
    (net (code "49") (name "TX") (class "Default")
      (node (ref "TP1") (pin "TP") (pinfunction "TP_TP") (pintype "input"))
      (node (ref "U2") (pin "25") (pinfunction "TXD0/GPIO16_25") (pintype "bidirectional"))
    )
    (net (code "50") (name "USB_D+") (class "Default")
      (node (ref "D1") (pin "1") (pinfunction "I/O1_1_1") (pintype "bidirectional"))
      (node (ref "U2") (pin "14") (pinfunction "IO13_14") (pintype "bidirectional"))
    )
    (net (code "51") (name "USB_D-") (class "Default")
      (node (ref "D1") (pin "3") (pinfunction "I/O2_1_3") (pintype "bidirectional"))
      (node (ref "U2") (pin "13") (pinfunction "IO12_13") (pintype "bidirectional"))
    )
    (net (code "52") (name "VBAT") (class "Default")
      (node (ref "C2_BAT") (pin "1") (pinfunction "1_1") (pintype "passive"))
      (node (ref "Q1") (pin "3") (pinfunction "D_3") (pintype "bidirectional"))
      (node (ref "TP3") (pin "TP") (pinfunction "TP_TP") (pintype "input"))
      (node (ref "U10") (pin "3") (pinfunction "VBAT_3") (pintype "power_in"))
      (node (ref "U4") (pin "2") (pinfunction "CELL_2") (pintype "power_in"))
      (node (ref "U4") (pin "3") (pinfunction "VDD_3") (pintype "power_in"))
    )
    (net (code "53") (name "VBUS") (class "Default")
      (node (ref "C1_BAT") (pin "1") (pinfunction "1_1") (pintype "passive"))
      (node (ref "C4_USB") (pin "1") (pinfunction "1_1") (pintype "passive"))
      (node (ref "C5_USB") (pin "1") (pinfunction "1_1") (pintype "passive"))
      (node (ref "CHG_LED") (pin "A") (pinfunction "A_A") (pintype "passive"))
      (node (ref "D1") (pin "5") (pinfunction "VBUS_5") (pintype "bidirectional"))
      (node (ref "D2") (pin "2") (pinfunction "ANODE_2") (pintype "bidirectional"))
      (node (ref "PFMF.050.1") (pin "2") (pinfunction "2_2") (pintype "passive"))
      (node (ref "Q1") (pin "1") (pinfunction "G_1") (pintype "bidirectional"))
      (node (ref "R1_PWRBUS") (pin "2") (pinfunction "2_2") (pintype "passive"))
      (node (ref "TP14") (pin "TP") (pinfunction "TP_TP") (pintype "input"))
      (node (ref "U10") (pin "4") (pinfunction "VIN_4") (pintype "power_in"))
    )
    (net (code "54") (name "VRTC") (class "Default")
      (node (ref "C10_SUPERCAP") (pin "2") (pinfunction "2_2") (pintype "passive"))
      (node (ref "C8") (pin "1") (pinfunction "1_1") (pintype "passive"))
      (node (ref "R_CAPACITOR") (pin "2") (pinfunction "2_2") (pintype "passive"))
      (node (ref "U3") (pin "14") (pinfunction "VBAT_14") (pintype "power_in"))
    )
    (net (code "55") (name "VUSB") (class "Default")
      (node (ref "J2") (pin "A4") (pinfunction "A4_A4") (pintype "bidirectional"))
      (node (ref "J2") (pin "A9") (pinfunction "A9_A9") (pintype "bidirectional"))
      (node (ref "J2") (pin "B4") (pinfunction "B4_B4") (pintype "bidirectional"))
      (node (ref "J2") (pin "B9") (pinfunction "B9_B9") (pintype "bidirectional"))
      (node (ref "PFMF.050.1") (pin "1") (pinfunction "1_1") (pintype "passive"))
    )
    (net (code "56") (name "unconnected-(IC1-NC-Pad4)") (class "Default")
      (node (ref "IC1") (pin "4") (pinfunction "NC_4") (pintype "no_connect"))
    )
    (net (code "57") (name "unconnected-(IC4-NC-Pad4)") (class "Default")
      (node (ref "IC4") (pin "4") (pinfunction "NC_4") (pintype "no_connect"))
    )
    (net (code "58") (name "unconnected-(J1-Pad1)") (class "Default")
      (node (ref "J1") (pin "1") (pinfunction "1_1") (pintype "bidirectional"))
    )
    (net (code "59") (name "unconnected-(J1-Pad6)") (class "Default")
      (node (ref "J1") (pin "6") (pinfunction "6_6") (pintype "bidirectional"))
    )
    (net (code "60") (name "unconnected-(J1-Pad7)") (class "Default")
      (node (ref "J1") (pin "7") (pinfunction "7_7") (pintype "bidirectional"))
    )
    (net (code "61") (name "unconnected-(J2-PadA8)") (class "Default")
      (node (ref "J2") (pin "A8") (pinfunction "A8_A8") (pintype "bidirectional"))
    )
    (net (code "62") (name "unconnected-(J2-PadB8)") (class "Default")
      (node (ref "J2") (pin "B8") (pinfunction "B8_B8") (pintype "bidirectional"))
    )
    (net (code "63") (name "unconnected-(J4-DAT1-PadP8)") (class "Default")
      (node (ref "J4") (pin "P8") (pinfunction "DAT1_P8") (pintype "bidirectional"))
    )
    (net (code "64") (name "unconnected-(J4-DAT2-PadP1)") (class "Default")
      (node (ref "J4") (pin "P1") (pinfunction "DAT2_P1") (pintype "bidirectional"))
    )
    (net (code "65") (name "unconnected-(J4-DETECTION_1-PadS1)") (class "Default")
      (node (ref "J4") (pin "S1") (pinfunction "DETECTION_1_S1") (pintype "bidirectional"))
    )
    (net (code "66") (name "unconnected-(J4-DETECTION_2-PadS2)") (class "Default")
      (node (ref "J4") (pin "S2") (pinfunction "DETECTION_2_S2") (pintype "bidirectional"))
    )
    (net (code "67") (name "unconnected-(U2-NC-Pad22)") (class "Default")
      (node (ref "U2") (pin "22") (pinfunction "NC_22") (pintype "no_connect"))
    )
    (net (code "68") (name "unconnected-(U4-~{ALERT}-Pad5)") (class "Default")
      (node (ref "U4") (pin "5") (pinfunction "~{ALERT}_5") (pintype "output"))
    )
  )
)
